# SCH_ECE198-11.net
KiCad netlist of a schematic drawn in EasyEDA
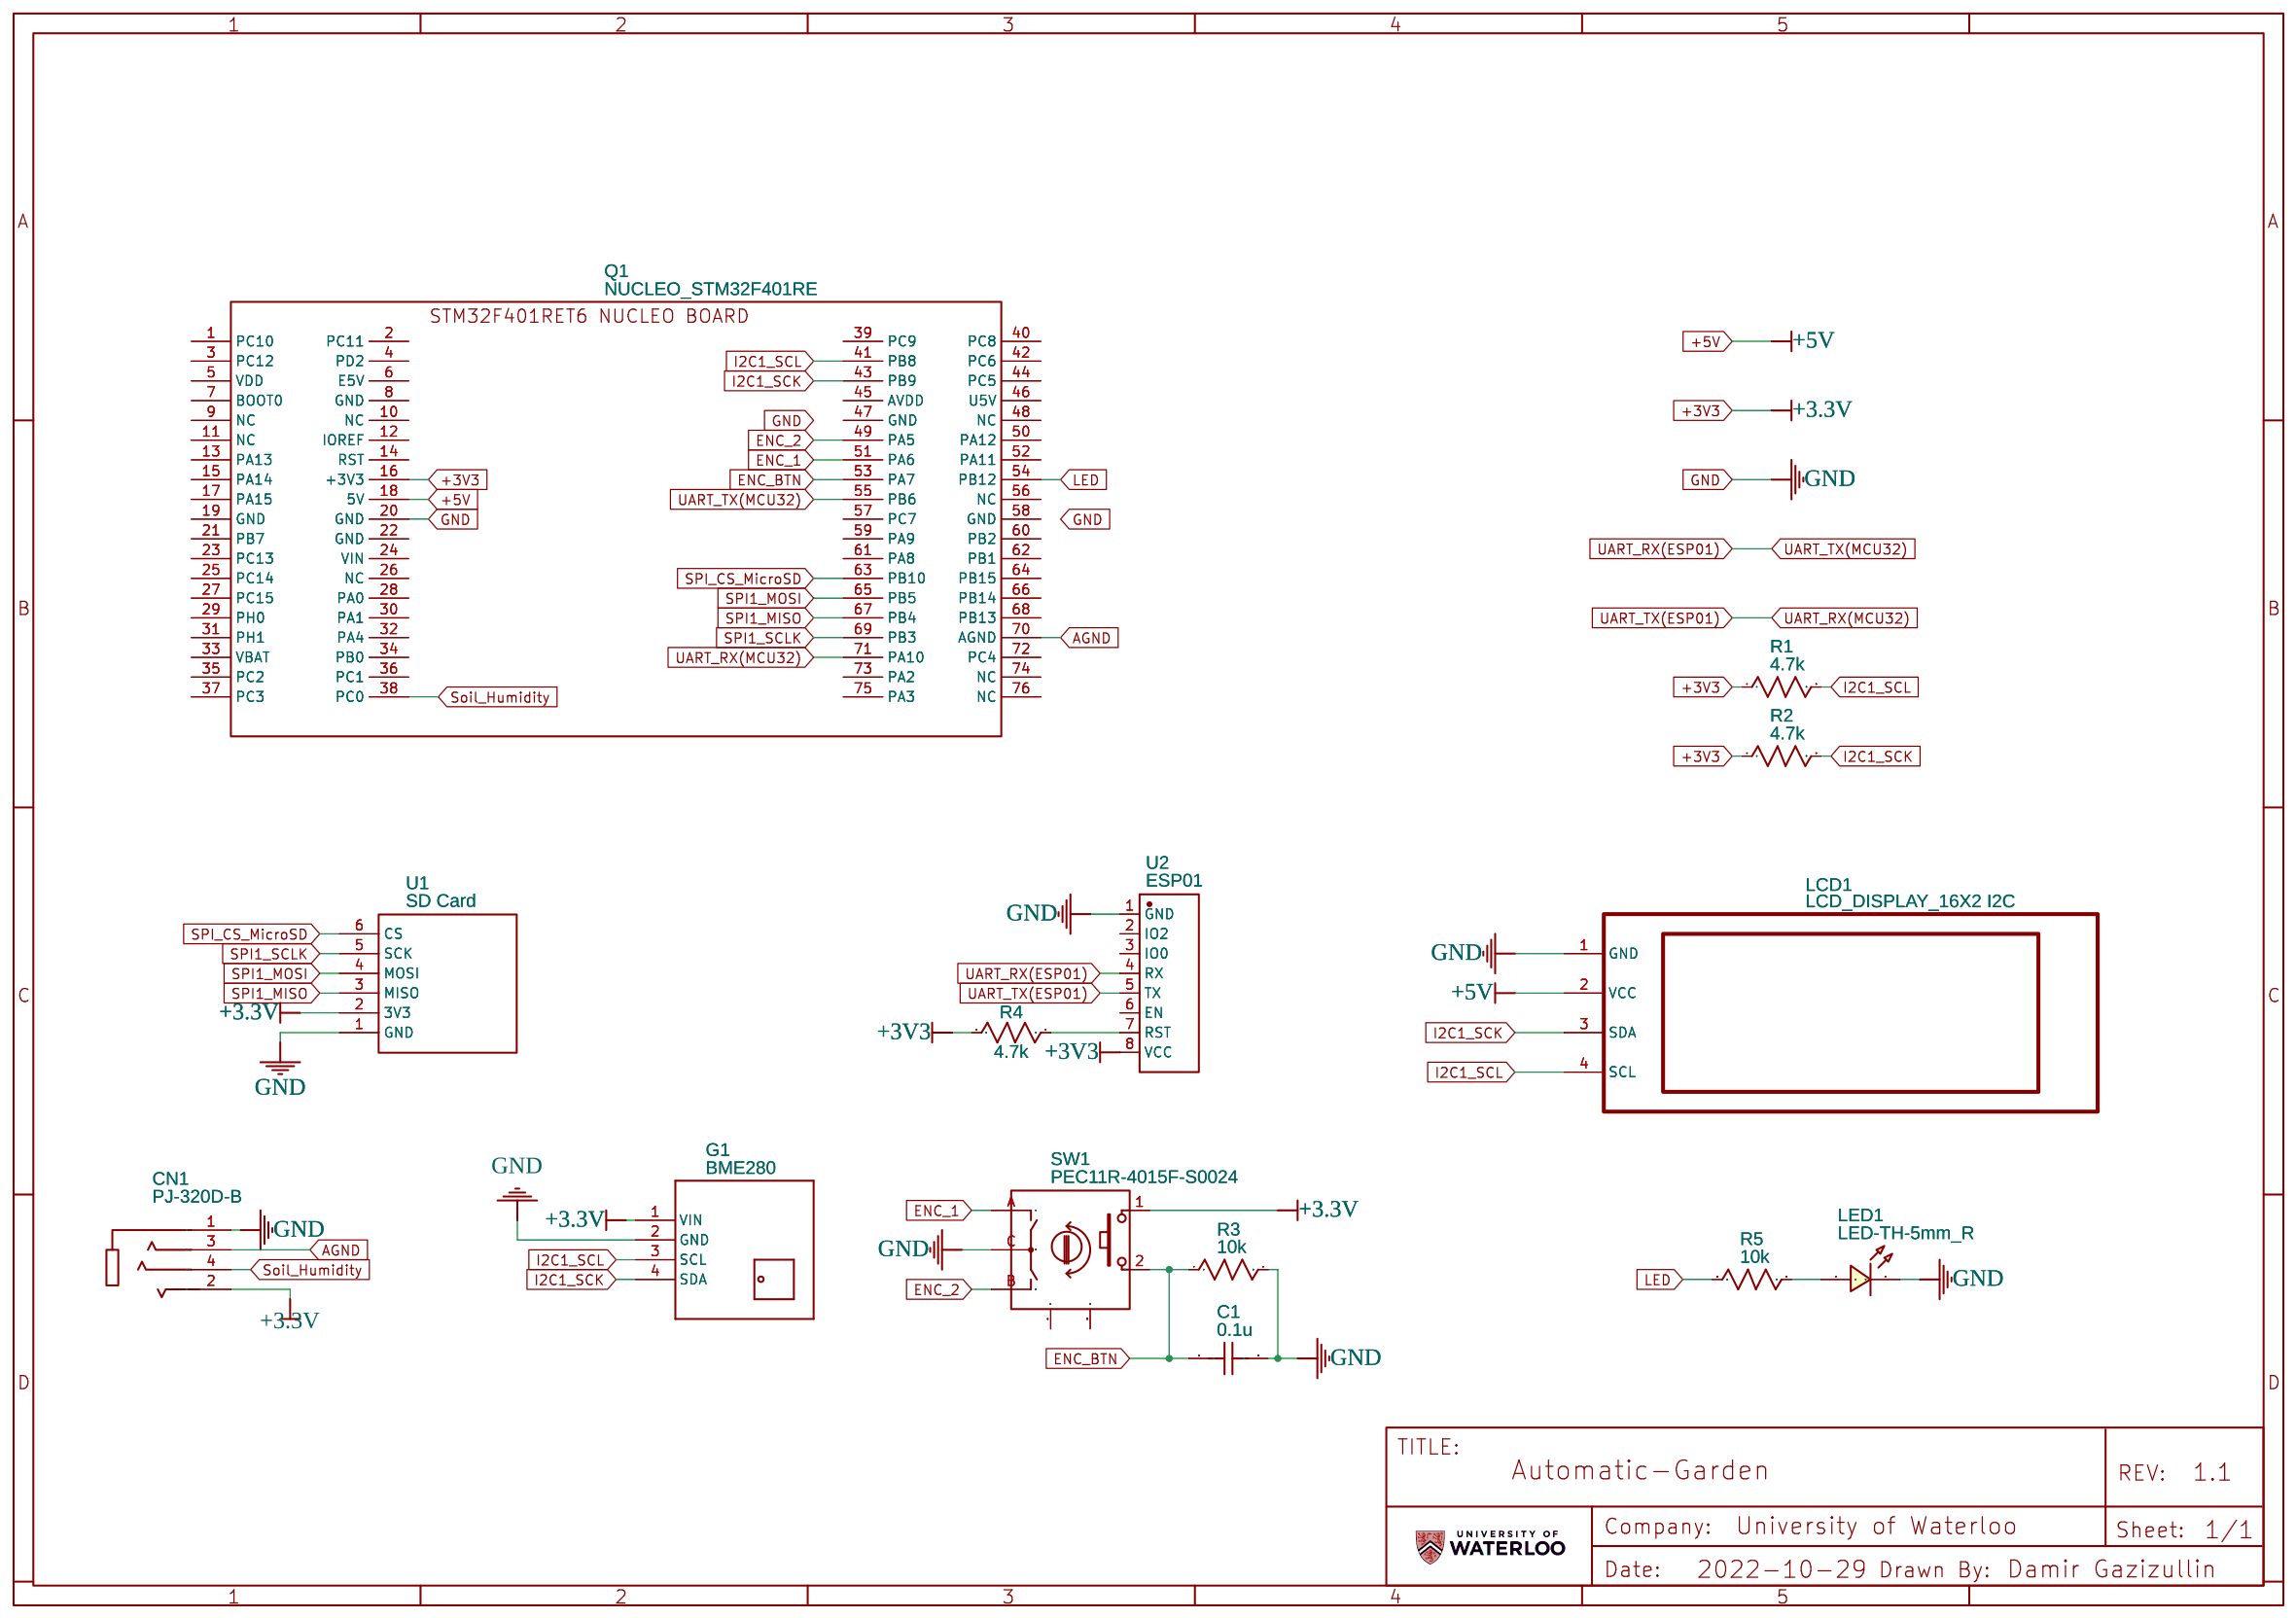
[diagram p0: schematic sheet]

(export (version "E")
  (design (tool "Eeschema 10.0.6"))
  (components
    (comp (ref "C1") (value "0.1u") (libsource (lib "") (part "C_0603_US")))
    (comp (ref "CN1")
      (value "PJ-320D-B")
      (fields (field (name "BOM_Supplier Part") "C2884940"))
      (libsource (lib "") (part "PJ-320D-B"))
    )
    (comp (ref "G1") (value "BME280") (libsource (lib "") (part "TEMP-HUM-PRES-BME280")))
    (comp (ref "LCD1") (value "LCD_DISPLAY_16X2 I2C") (libsource (lib "") (part "LCD_DISPLAY_16X2 I2C")))
    (comp (ref "LED1")
      (value "LED-TH-5mm_R")
      (fields
        (field (name "BOM_Manufacturer Part") "333-2SURD/S530-A3")
        (field (name "BOM_Supplier Part") "C87271")
      )
      (libsource (lib "") (part "LED-TH-5mm_R"))
    )
    (comp (ref "Q1") (value "NUCLEO_STM32F401RE") (libsource (lib "") (part "NUCLEO_STM32F401RE")))
    (comp (ref "R1") (value "4.7k") (libsource (lib "") (part "R_0603_US")))
    (comp (ref "R2") (value "4.7k") (libsource (lib "") (part "R_0603_US")))
    (comp (ref "R3") (value "10k") (libsource (lib "") (part "R_AXIAL-0.5_US_1")))
    (comp (ref "R4") (value "4.7k") (libsource (lib "") (part "R_AXIAL-0.5_US_1")))
    (comp (ref "R5") (value "10k") (libsource (lib "") (part "R_AXIAL-0.5_US")))
    (comp (ref "SW1")
      (value "PEC11R-4015F-S0024")
      (fields (field (name "BOM_Supplier Part") "C143789"))
      (libsource (lib "") (part "PEC11R-4015F-S0024"))
    )
    (comp (ref "U1") (value "SD Card") (libsource (lib "") (part "SD Card")))
    (comp (ref "U2") (value "ESP01") (libsource (lib "") (part "ESP01")))
  )
  (nets
    (net (code "1") (name "+3V3") (class "Default")
      (node (ref "CN1") (pin "2") (pinfunction "2_2") (pintype "unspecified"))
      (node (ref "G1") (pin "1") (pinfunction "VIN_1") (pintype "bidirectional"))
      (node (ref "Q1") (pin "16") (pinfunction "+3V3_16") (pintype "unspecified"))
      (node (ref "R1") (pin "1") (pinfunction "1_1") (pintype "unspecified"))
      (node (ref "R2") (pin "1") (pinfunction "1_1") (pintype "unspecified"))
      (node (ref "R4") (pin "1") (pinfunction "1_1") (pintype "unspecified"))
      (node (ref "SW1") (pin "1") (pinfunction "1_1") (pintype "unspecified"))
      (node (ref "U1") (pin "2") (pinfunction "3V3_2") (pintype "unspecified"))
      (node (ref "U2") (pin "8") (pinfunction "VCC_8") (pintype "unspecified"))
    )
    (net (code "2") (name "+5V") (class "Default")
      (node (ref "LCD1") (pin "2") (pinfunction "VCC_2") (pintype "passive"))
      (node (ref "Q1") (pin "18") (pinfunction "5V_18") (pintype "unspecified"))
    )
    (net (code "3") (name "AGND") (class "Default")
      (node (ref "CN1") (pin "3") (pinfunction "3_3") (pintype "unspecified"))
      (node (ref "Q1") (pin "70") (pinfunction "AGND_70") (pintype "unspecified"))
    )
    (net (code "4") (name "ENC_1") (class "Default")
      (node (ref "Q1") (pin "51") (pinfunction "PA6_51") (pintype "unspecified"))
      (node (ref "SW1") (pin "A") (pinfunction "A_A") (pintype "unspecified"))
    )
    (net (code "5") (name "ENC_2") (class "Default")
      (node (ref "Q1") (pin "49") (pinfunction "PA5_49") (pintype "unspecified"))
      (node (ref "SW1") (pin "B") (pinfunction "B_B") (pintype "unspecified"))
    )
    (net (code "6") (name "ENC_BTN") (class "Default")
      (node (ref "C1") (pin "1") (pinfunction "1_1") (pintype "unspecified"))
      (node (ref "Q1") (pin "53") (pinfunction "PA7_53") (pintype "unspecified"))
      (node (ref "R3") (pin "1") (pinfunction "1_1") (pintype "unspecified"))
      (node (ref "SW1") (pin "2") (pinfunction "2_2") (pintype "unspecified"))
    )
    (net (code "7") (name "GND") (class "Default")
      (node (ref "C1") (pin "2") (pinfunction "2_2") (pintype "unspecified"))
      (node (ref "CN1") (pin "1") (pinfunction "1_1") (pintype "unspecified"))
      (node (ref "G1") (pin "2") (pinfunction "GND_2") (pintype "bidirectional"))
      (node (ref "LCD1") (pin "1") (pinfunction "GND_1") (pintype "passive"))
      (node (ref "LED1") (pin "2") (pinfunction "2_2") (pintype "unspecified"))
      (node (ref "Q1") (pin "20") (pinfunction "GND_20") (pintype "unspecified"))
      (node (ref "R3") (pin "2") (pinfunction "2_2") (pintype "unspecified"))
      (node (ref "SW1") (pin "C") (pinfunction "C_C") (pintype "unspecified"))
      (node (ref "U1") (pin "1") (pinfunction "GND_1") (pintype "unspecified"))
      (node (ref "U2") (pin "1") (pinfunction "GND_1") (pintype "unspecified"))
    )
    (net (code "8") (name "I2C1_SCK") (class "Default")
      (node (ref "G1") (pin "4") (pinfunction "SDA_4") (pintype "bidirectional"))
      (node (ref "LCD1") (pin "3") (pinfunction "SDA_3") (pintype "passive"))
      (node (ref "Q1") (pin "43") (pinfunction "PB9_43") (pintype "unspecified"))
      (node (ref "R2") (pin "2") (pinfunction "2_2") (pintype "unspecified"))
    )
    (net (code "9") (name "I2C1_SCL") (class "Default")
      (node (ref "G1") (pin "3") (pinfunction "SCL_3") (pintype "bidirectional"))
      (node (ref "LCD1") (pin "4") (pinfunction "SCL_4") (pintype "passive"))
      (node (ref "Q1") (pin "41") (pinfunction "PB8_41") (pintype "unspecified"))
      (node (ref "R1") (pin "2") (pinfunction "2_2") (pintype "unspecified"))
    )
    (net (code "10") (name "LED") (class "Default")
      (node (ref "Q1") (pin "54") (pinfunction "PB12_54") (pintype "unspecified"))
      (node (ref "R5") (pin "2") (pinfunction "2_2") (pintype "unspecified"))
    )
    (net (code "11") (name "Net-(LED1-Pad1)") (class "Default")
      (node (ref "LED1") (pin "1") (pinfunction "1_1") (pintype "unspecified"))
      (node (ref "R5") (pin "1") (pinfunction "1_1") (pintype "unspecified"))
    )
    (net (code "12") (name "Net-(U2-RST)") (class "Default")
      (node (ref "R4") (pin "2") (pinfunction "2_2") (pintype "unspecified"))
      (node (ref "U2") (pin "7") (pinfunction "RST_7") (pintype "unspecified"))
    )
    (net (code "13") (name "SPI1_MISO") (class "Default")
      (node (ref "Q1") (pin "67") (pinfunction "PB4_67") (pintype "unspecified"))
      (node (ref "U1") (pin "3") (pinfunction "MISO_3") (pintype "unspecified"))
    )
    (net (code "14") (name "SPI1_MOSI") (class "Default")
      (node (ref "Q1") (pin "65") (pinfunction "PB5_65") (pintype "unspecified"))
      (node (ref "U1") (pin "4") (pinfunction "MOSI_4") (pintype "unspecified"))
    )
    (net (code "15") (name "SPI1_SCLK") (class "Default")
      (node (ref "Q1") (pin "69") (pinfunction "PB3_69") (pintype "unspecified"))
      (node (ref "U1") (pin "5") (pinfunction "SCK_5") (pintype "unspecified"))
    )
    (net (code "16") (name "SPI_CS_MicroSD") (class "Default")
      (node (ref "Q1") (pin "63") (pinfunction "PB10_63") (pintype "unspecified"))
      (node (ref "U1") (pin "6") (pinfunction "CS_6") (pintype "unspecified"))
    )
    (net (code "17") (name "Soil_Humidity") (class "Default")
      (node (ref "CN1") (pin "4") (pinfunction "4_4") (pintype "unspecified"))
      (node (ref "Q1") (pin "38") (pinfunction "PC0_38") (pintype "unspecified"))
    )
    (net (code "18") (name "UART_RX(ESP01)") (class "Default")
      (node (ref "Q1") (pin "55") (pinfunction "PB6_55") (pintype "unspecified"))
      (node (ref "U2") (pin "4") (pinfunction "RX_4") (pintype "unspecified"))
    )
    (net (code "19") (name "UART_RX(MCU32)") (class "Default")
      (node (ref "Q1") (pin "71") (pinfunction "PA10_71") (pintype "unspecified"))
      (node (ref "U2") (pin "5") (pinfunction "TX_5") (pintype "unspecified"))
    )
    (net (code "20") (name "unconnected-(Q1-AVDD-Pad45)") (class "Default")
      (node (ref "Q1") (pin "45") (pinfunction "AVDD_45") (pintype "unspecified"))
    )
    (net (code "21") (name "unconnected-(Q1-BOOT0-Pad7)") (class "Default")
      (node (ref "Q1") (pin "7") (pinfunction "BOOT0_7") (pintype "unspecified"))
    )
    (net (code "22") (name "unconnected-(Q1-E5V-Pad6)") (class "Default")
      (node (ref "Q1") (pin "6") (pinfunction "E5V_6") (pintype "unspecified"))
    )
    (net (code "23") (name "unconnected-(Q1-GND-Pad8)") (class "Default")
      (node (ref "Q1") (pin "8") (pinfunction "GND_8") (pintype "unspecified"))
    )
    (net (code "24") (name "unconnected-(Q1-GND-Pad19)") (class "Default")
      (node (ref "Q1") (pin "19") (pinfunction "GND_19") (pintype "unspecified"))
    )
    (net (code "25") (name "unconnected-(Q1-GND-Pad22)") (class "Default")
      (node (ref "Q1") (pin "22") (pinfunction "GND_22") (pintype "unspecified"))
    )
    (net (code "26") (name "unconnected-(Q1-GND-Pad47)") (class "Default")
      (node (ref "Q1") (pin "47") (pinfunction "GND_47") (pintype "unspecified"))
    )
    (net (code "27") (name "unconnected-(Q1-GND-Pad58)") (class "Default")
      (node (ref "Q1") (pin "58") (pinfunction "GND_58") (pintype "unspecified"))
    )
    (net (code "28") (name "unconnected-(Q1-IOREF-Pad12)") (class "Default")
      (node (ref "Q1") (pin "12") (pinfunction "IOREF_12") (pintype "unspecified"))
    )
    (net (code "29") (name "unconnected-(Q1-NC-Pad9)") (class "Default")
      (node (ref "Q1") (pin "9") (pinfunction "NC_9") (pintype "unspecified"))
    )
    (net (code "30") (name "unconnected-(Q1-NC-Pad10)") (class "Default")
      (node (ref "Q1") (pin "10") (pinfunction "NC_10") (pintype "unspecified"))
    )
    (net (code "31") (name "unconnected-(Q1-NC-Pad11)") (class "Default")
      (node (ref "Q1") (pin "11") (pinfunction "NC_11") (pintype "unspecified"))
    )
    (net (code "32") (name "unconnected-(Q1-NC-Pad26)") (class "Default")
      (node (ref "Q1") (pin "26") (pinfunction "NC_26") (pintype "unspecified"))
    )
    (net (code "33") (name "unconnected-(Q1-NC-Pad48)") (class "Default")
      (node (ref "Q1") (pin "48") (pinfunction "NC_48") (pintype "unspecified"))
    )
    (net (code "34") (name "unconnected-(Q1-NC-Pad56)") (class "Default")
      (node (ref "Q1") (pin "56") (pinfunction "NC_56") (pintype "unspecified"))
    )
    (net (code "35") (name "unconnected-(Q1-NC-Pad74)") (class "Default")
      (node (ref "Q1") (pin "74") (pinfunction "NC_74") (pintype "unspecified"))
    )
    (net (code "36") (name "unconnected-(Q1-NC-Pad76)") (class "Default")
      (node (ref "Q1") (pin "76") (pinfunction "NC_76") (pintype "unspecified"))
    )
    (net (code "37") (name "unconnected-(Q1-PA0-Pad28)") (class "Default")
      (node (ref "Q1") (pin "28") (pinfunction "PA0_28") (pintype "unspecified"))
    )
    (net (code "38") (name "unconnected-(Q1-PA1-Pad30)") (class "Default")
      (node (ref "Q1") (pin "30") (pinfunction "PA1_30") (pintype "unspecified"))
    )
    (net (code "39") (name "unconnected-(Q1-PA2-Pad73)") (class "Default")
      (node (ref "Q1") (pin "73") (pinfunction "PA2_73") (pintype "unspecified"))
    )
    (net (code "40") (name "unconnected-(Q1-PA3-Pad75)") (class "Default")
      (node (ref "Q1") (pin "75") (pinfunction "PA3_75") (pintype "unspecified"))
    )
    (net (code "41") (name "unconnected-(Q1-PA4-Pad32)") (class "Default")
      (node (ref "Q1") (pin "32") (pinfunction "PA4_32") (pintype "unspecified"))
    )
    (net (code "42") (name "unconnected-(Q1-PA8-Pad61)") (class "Default")
      (node (ref "Q1") (pin "61") (pinfunction "PA8_61") (pintype "unspecified"))
    )
    (net (code "43") (name "unconnected-(Q1-PA9-Pad59)") (class "Default")
      (node (ref "Q1") (pin "59") (pinfunction "PA9_59") (pintype "unspecified"))
    )
    (net (code "44") (name "unconnected-(Q1-PA11-Pad52)") (class "Default")
      (node (ref "Q1") (pin "52") (pinfunction "PA11_52") (pintype "unspecified"))
    )
    (net (code "45") (name "unconnected-(Q1-PA12-Pad50)") (class "Default")
      (node (ref "Q1") (pin "50") (pinfunction "PA12_50") (pintype "unspecified"))
    )
    (net (code "46") (name "unconnected-(Q1-PA13-Pad13)") (class "Default")
      (node (ref "Q1") (pin "13") (pinfunction "PA13_13") (pintype "unspecified"))
    )
    (net (code "47") (name "unconnected-(Q1-PA14-Pad15)") (class "Default")
      (node (ref "Q1") (pin "15") (pinfunction "PA14_15") (pintype "unspecified"))
    )
    (net (code "48") (name "unconnected-(Q1-PA15-Pad17)") (class "Default")
      (node (ref "Q1") (pin "17") (pinfunction "PA15_17") (pintype "unspecified"))
    )
    (net (code "49") (name "unconnected-(Q1-PB0-Pad34)") (class "Default")
      (node (ref "Q1") (pin "34") (pinfunction "PB0_34") (pintype "unspecified"))
    )
    (net (code "50") (name "unconnected-(Q1-PB1-Pad62)") (class "Default")
      (node (ref "Q1") (pin "62") (pinfunction "PB1_62") (pintype "unspecified"))
    )
    (net (code "51") (name "unconnected-(Q1-PB2-Pad60)") (class "Default")
      (node (ref "Q1") (pin "60") (pinfunction "PB2_60") (pintype "unspecified"))
    )
    (net (code "52") (name "unconnected-(Q1-PB7-Pad21)") (class "Default")
      (node (ref "Q1") (pin "21") (pinfunction "PB7_21") (pintype "unspecified"))
    )
    (net (code "53") (name "unconnected-(Q1-PB13-Pad68)") (class "Default")
      (node (ref "Q1") (pin "68") (pinfunction "PB13_68") (pintype "unspecified"))
    )
    (net (code "54") (name "unconnected-(Q1-PB14-Pad66)") (class "Default")
      (node (ref "Q1") (pin "66") (pinfunction "PB14_66") (pintype "unspecified"))
    )
    (net (code "55") (name "unconnected-(Q1-PB15-Pad64)") (class "Default")
      (node (ref "Q1") (pin "64") (pinfunction "PB15_64") (pintype "unspecified"))
    )
    (net (code "56") (name "unconnected-(Q1-PC1-Pad36)") (class "Default")
      (node (ref "Q1") (pin "36") (pinfunction "PC1_36") (pintype "unspecified"))
    )
    (net (code "57") (name "unconnected-(Q1-PC2-Pad35)") (class "Default")
      (node (ref "Q1") (pin "35") (pinfunction "PC2_35") (pintype "unspecified"))
    )
    (net (code "58") (name "unconnected-(Q1-PC3-Pad37)") (class "Default")
      (node (ref "Q1") (pin "37") (pinfunction "PC3_37") (pintype "unspecified"))
    )
    (net (code "59") (name "unconnected-(Q1-PC4-Pad72)") (class "Default")
      (node (ref "Q1") (pin "72") (pinfunction "PC4_72") (pintype "unspecified"))
    )
    (net (code "60") (name "unconnected-(Q1-PC5-Pad44)") (class "Default")
      (node (ref "Q1") (pin "44") (pinfunction "PC5_44") (pintype "unspecified"))
    )
    (net (code "61") (name "unconnected-(Q1-PC6-Pad42)") (class "Default")
      (node (ref "Q1") (pin "42") (pinfunction "PC6_42") (pintype "unspecified"))
    )
    (net (code "62") (name "unconnected-(Q1-PC7-Pad57)") (class "Default")
      (node (ref "Q1") (pin "57") (pinfunction "PC7_57") (pintype "unspecified"))
    )
    (net (code "63") (name "unconnected-(Q1-PC8-Pad40)") (class "Default")
      (node (ref "Q1") (pin "40") (pinfunction "PC8_40") (pintype "unspecified"))
    )
    (net (code "64") (name "unconnected-(Q1-PC9-Pad39)") (class "Default")
      (node (ref "Q1") (pin "39") (pinfunction "PC9_39") (pintype "unspecified"))
    )
    (net (code "65") (name "unconnected-(Q1-PC10-Pad1)") (class "Default")
      (node (ref "Q1") (pin "1") (pinfunction "PC10_1") (pintype "unspecified"))
    )
    (net (code "66") (name "unconnected-(Q1-PC11-Pad2)") (class "Default")
      (node (ref "Q1") (pin "2") (pinfunction "PC11_2") (pintype "unspecified"))
    )
    (net (code "67") (name "unconnected-(Q1-PC12-Pad3)") (class "Default")
      (node (ref "Q1") (pin "3") (pinfunction "PC12_3") (pintype "unspecified"))
    )
    (net (code "68") (name "unconnected-(Q1-PC13-Pad23)") (class "Default")
      (node (ref "Q1") (pin "23") (pinfunction "PC13_23") (pintype "unspecified"))
    )
    (net (code "69") (name "unconnected-(Q1-PC14-Pad25)") (class "Default")
      (node (ref "Q1") (pin "25") (pinfunction "PC14_25") (pintype "unspecified"))
    )
    (net (code "70") (name "unconnected-(Q1-PC15-Pad27)") (class "Default")
      (node (ref "Q1") (pin "27") (pinfunction "PC15_27") (pintype "unspecified"))
    )
    (net (code "71") (name "unconnected-(Q1-PD2-Pad4)") (class "Default")
      (node (ref "Q1") (pin "4") (pinfunction "PD2_4") (pintype "unspecified"))
    )
    (net (code "72") (name "unconnected-(Q1-PH0-Pad29)") (class "Default")
      (node (ref "Q1") (pin "29") (pinfunction "PH0_29") (pintype "unspecified"))
    )
    (net (code "73") (name "unconnected-(Q1-PH1-Pad31)") (class "Default")
      (node (ref "Q1") (pin "31") (pinfunction "PH1_31") (pintype "unspecified"))
    )
    (net (code "74") (name "unconnected-(Q1-RST-Pad14)") (class "Default")
      (node (ref "Q1") (pin "14") (pinfunction "RST_14") (pintype "unspecified"))
    )
    (net (code "75") (name "unconnected-(Q1-U5V-Pad46)") (class "Default")
      (node (ref "Q1") (pin "46") (pinfunction "U5V_46") (pintype "unspecified"))
    )
    (net (code "76") (name "unconnected-(Q1-VBAT-Pad33)") (class "Default")
      (node (ref "Q1") (pin "33") (pinfunction "VBAT_33") (pintype "unspecified"))
    )
    (net (code "77") (name "unconnected-(Q1-VDD-Pad5)") (class "Default")
      (node (ref "Q1") (pin "5") (pinfunction "VDD_5") (pintype "unspecified"))
    )
    (net (code "78") (name "unconnected-(Q1-VIN-Pad24)") (class "Default")
      (node (ref "Q1") (pin "24") (pinfunction "VIN_24") (pintype "unspecified"))
    )
    (net (code "79") (name "unconnected-(SW1-PadMT1)") (class "Default")
      (node (ref "SW1") (pin "MT1") (pinfunction "MT1_MT1") (pintype "unspecified"))
    )
    (net (code "80") (name "unconnected-(SW1-PadMT2)") (class "Default")
      (node (ref "SW1") (pin "MT2") (pinfunction "MT2_MT2") (pintype "unspecified"))
    )
    (net (code "81") (name "unconnected-(U2-EN-Pad6)") (class "Default")
      (node (ref "U2") (pin "6") (pinfunction "EN_6") (pintype "unspecified"))
    )
    (net (code "82") (name "unconnected-(U2-IO0-Pad3)") (class "Default")
      (node (ref "U2") (pin "3") (pinfunction "IO0_3") (pintype "unspecified"))
    )
    (net (code "83") (name "unconnected-(U2-IO2-Pad2)") (class "Default")
      (node (ref "U2") (pin "2") (pinfunction "IO2_2") (pintype "unspecified"))
    )
  )
)
